# rely_pcb.net
KiCad netlist of a schematic drawn in EAGLE
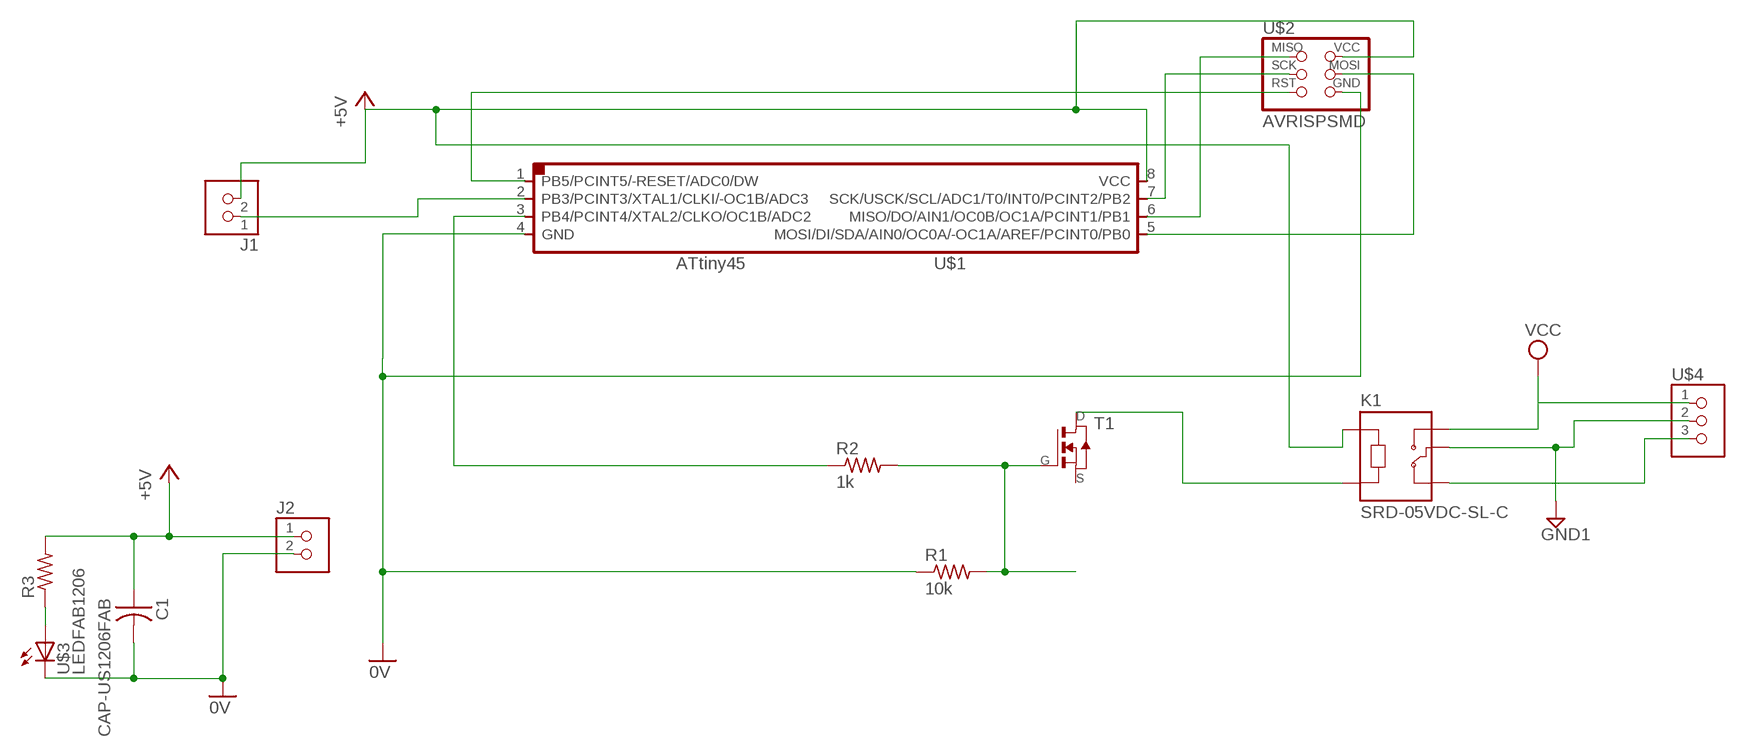
[diagram p0: schematic, sheet 1]

(export (version "E")
  (design (tool "Eeschema 10.0.6"))
  (components
    (comp (ref "C1")
      (value "CAP-US1206FAB")
      (footprint "eagle-import:C1206FAB")
      (libsource (lib "eagle-import") (part "CAP-US1206FAB"))
    )
    (comp (ref "J1")
      (value "TERM-1X02-ADAFRUIT")
      (footprint "eagle-import:3.5MMTERM")
      (libsource (lib "eagle-import") (part "TERM-1X02-ADAFRUIT"))
    )
    (comp (ref "J2")
      (value "TERM-1X02-ADAFRUIT")
      (footprint "eagle-import:3.5MMTERM")
      (libsource (lib "eagle-import") (part "TERM-1X02-ADAFRUIT"))
    )
    (comp (ref "K1")
      (value "SRD-05VDC-SL-C")
      (footprint "eagle-import:RELAY_SRD-05VDC-SL-C")
      (fields (field (name "MF") "Songle Relay"))
      (libsource (lib "eagle-import") (part "SRD-05VDC-SL-C"))
    )
    (comp (ref "R1")
      (value "10k")
      (footprint "eagle-import:R1206FAB")
      (libsource (lib "eagle-import") (part "RES-US1206FAB"))
    )
    (comp (ref "R2")
      (value "1k")
      (footprint "eagle-import:R1206FAB")
      (libsource (lib "eagle-import") (part "RES-US1206FAB"))
    )
    (comp (ref "R3")
      (value "RES-US1206FAB")
      (footprint "eagle-import:R1206FAB")
      (libsource (lib "eagle-import") (part "RES-US1206FAB"))
    )
    (comp (ref "T1")
      (value "NMOSFETTO252")
      (footprint "eagle-import:TO252")
      (libsource (lib "eagle-import") (part "NMOSFETTO252"))
    )
    (comp (ref "U$1")
      (value "ATTINY45SI")
      (footprint "eagle-import:SOIC8")
      (libsource (lib "eagle-import") (part "ATTINY45SI"))
    )
    (comp (ref "U$2")
      (value "AVRISPSMD")
      (footprint "eagle-import:2X03SMD")
      (libsource (lib "eagle-import") (part "AVRISPSMD"))
    )
    (comp (ref "U$3")
      (value "LEDFAB1206")
      (footprint "eagle-import:LED1206FAB")
      (libsource (lib "eagle-import") (part "LEDFAB1206"))
    )
    (comp (ref "U$4")
      (value "TERM-1X03'-FABLAB'")
      (footprint "eagle-import:ED555DS-3DS")
      (libsource (lib "eagle-import") (part "TERM-1X03'-FABLAB'"))
    )
  )
  (nets
    (net (code "1") (name "+5V") (class "Default")
      (node (ref "C1") (pin "1") (pinfunction "1_1") (pintype "passive"))
      (node (ref "J1") (pin "2") (pinfunction "2_2") (pintype "passive"))
      (node (ref "J2") (pin "1") (pinfunction "1_1") (pintype "passive"))
      (node (ref "K1") (pin "A1") (pinfunction "A1_A1") (pintype "passive"))
      (node (ref "R3") (pin "2") (pinfunction "2_2") (pintype "passive"))
      (node (ref "U$1") (pin "8") (pinfunction "VCC_8") (pintype "bidirectional"))
      (node (ref "U$2") (pin "2") (pinfunction "VCC_2") (pintype "passive"))
    )
    (net (code "2") (name "0V") (class "Default")
      (node (ref "C1") (pin "2") (pinfunction "2_2") (pintype "passive"))
      (node (ref "J2") (pin "2") (pinfunction "2_2") (pintype "passive"))
      (node (ref "R1") (pin "1") (pinfunction "1_1") (pintype "passive"))
      (node (ref "U$1") (pin "4") (pinfunction "GND_4") (pintype "bidirectional"))
      (node (ref "U$2") (pin "6") (pinfunction "GND_6") (pintype "passive"))
      (node (ref "U$3") (pin "2") (pinfunction "C_2") (pintype "passive"))
    )
    (net (code "3") (name "GND1") (class "Default")
      (node (ref "K1") (pin "COM") (pinfunction "COM_COM") (pintype "passive"))
      (node (ref "U$4") (pin "2") (pinfunction "2_2") (pintype "passive"))
    )
    (net (code "4") (name "Net-(K1-PadNC)") (class "Default")
      (node (ref "K1") (pin "NC") (pinfunction "NC_NC") (pintype "passive"))
      (node (ref "U$4") (pin "3") (pinfunction "3_3") (pintype "passive"))
    )
    (net (code "5") (name "Net-(T1-D)") (class "Default")
      (node (ref "K1") (pin "A2") (pinfunction "A2_A2") (pintype "passive"))
      (node (ref "T1") (pin "3") (pinfunction "D_3") (pintype "passive"))
    )
    (net (code "6") (name "Net-(T1-G)") (class "Default")
      (node (ref "R1") (pin "2") (pinfunction "2_2") (pintype "passive"))
      (node (ref "R2") (pin "2") (pinfunction "2_2") (pintype "passive"))
      (node (ref "T1") (pin "1") (pinfunction "G_1") (pintype "passive"))
    )
    (net (code "7") (name "Net-(U$1-MISO{slash}DO{slash}AIN1{slash}OC0B{slash}OC1A{slash}PCINT1{slash}PB1)") (class "Default")
      (node (ref "U$1") (pin "6") (pinfunction "MISO/DO/AIN1/OC0B/OC1A/PCINT1/PB1_6") (pintype "bidirectional"))
      (node (ref "U$2") (pin "1") (pinfunction "MISO_1") (pintype "passive"))
    )
    (net (code "8") (name "Net-(U$1-MOSI{slash}DI{slash}SDA{slash}AIN0{slash}OC0A{slash}-OC1A{slash}AREF{slash}PCINT0{slash}PB0)") (class "Default")
      (node (ref "U$1") (pin "5") (pinfunction "MOSI/DI/SDA/AIN0/OC0A/-OC1A/AREF/PCINT0/PB0_5") (pintype "bidirectional"))
      (node (ref "U$2") (pin "4") (pinfunction "MOSI_4") (pintype "passive"))
    )
    (net (code "9") (name "Net-(U$1-PB3{slash}PCINT3{slash}XTAL1{slash}CLKI{slash}-OC1B{slash}ADC3)") (class "Default")
      (node (ref "J1") (pin "1") (pinfunction "1_1") (pintype "passive"))
      (node (ref "U$1") (pin "2") (pinfunction "PB3/PCINT3/XTAL1/CLKI/-OC1B/ADC3_2") (pintype "bidirectional"))
    )
    (net (code "10") (name "Net-(U$1-PB4{slash}PCINT4{slash}XTAL2{slash}CLKO{slash}OC1B{slash}ADC2)") (class "Default")
      (node (ref "R2") (pin "1") (pinfunction "1_1") (pintype "passive"))
      (node (ref "U$1") (pin "3") (pinfunction "PB4/PCINT4/XTAL2/CLKO/OC1B/ADC2_3") (pintype "bidirectional"))
    )
    (net (code "11") (name "Net-(U$1-PB5{slash}PCINT5{slash}-RESET{slash}ADC0{slash}DW)") (class "Default")
      (node (ref "U$1") (pin "1") (pinfunction "PB5/PCINT5/-RESET/ADC0/DW_1") (pintype "bidirectional"))
      (node (ref "U$2") (pin "5") (pinfunction "RST_5") (pintype "passive"))
    )
    (net (code "12") (name "Net-(U$1-SCK{slash}USCK{slash}SCL{slash}ADC1{slash}T0{slash}INT0{slash}PCINT2{slash}PB2)") (class "Default")
      (node (ref "U$1") (pin "7") (pinfunction "SCK/USCK/SCL/ADC1/T0/INT0/PCINT2/PB2_7") (pintype "bidirectional"))
      (node (ref "U$2") (pin "3") (pinfunction "SCK_3") (pintype "passive"))
    )
    (net (code "13") (name "Net-(U$3-A)") (class "Default")
      (node (ref "R3") (pin "1") (pinfunction "1_1") (pintype "passive"))
      (node (ref "U$3") (pin "1") (pinfunction "A_1") (pintype "passive"))
    )
    (net (code "14") (name "VCC") (class "Default")
      (node (ref "K1") (pin "NO") (pinfunction "NO_NO") (pintype "passive"))
      (node (ref "U$4") (pin "1") (pinfunction "1_1") (pintype "passive"))
    )
    (net (code "15") (name "unconnected-(T1-S-Pad2)") (class "Default")
      (node (ref "T1") (pin "2") (pinfunction "S_2") (pintype "passive"))
    )
  )
)
